# UM7_Schematic.net
KiCad netlist of a schematic drawn in Altium Designer
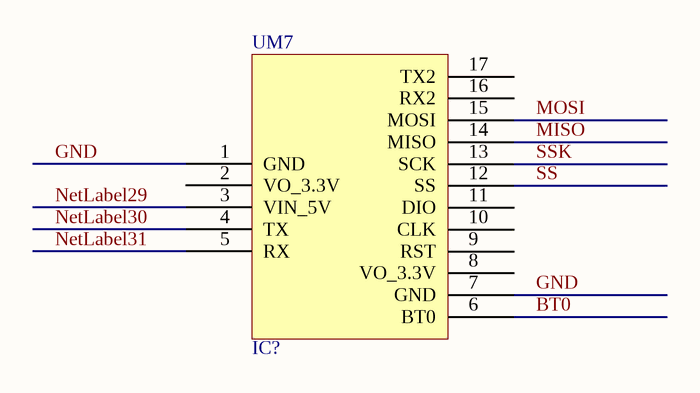
[diagram p0: UM7_Schematic.SchDoc]

(export (version "E")
  (design (tool "Eeschema 10.0.6"))
  (components (comp (ref "UM7") (value "IC?") (libsource (lib "UM7") (part "IC?"))))
  (nets
    (net (code "1") (name "/BT0") (class "Default")
      (node (ref "UM7") (pin "6") (pinfunction "BT0_6") (pintype "passive"))
    )
    (net (code "2") (name "/GND") (class "Default")
      (node (ref "UM7") (pin "1") (pinfunction "GND_1") (pintype "passive"))
      (node (ref "UM7") (pin "7") (pinfunction "GND_7") (pintype "passive"))
    )
    (net (code "3") (name "/MISO") (class "Default")
      (node (ref "UM7") (pin "14") (pinfunction "MISO_14") (pintype "passive"))
    )
    (net (code "4") (name "/MOSI") (class "Default")
      (node (ref "UM7") (pin "15") (pinfunction "MOSI_15") (pintype "passive"))
    )
    (net (code "5") (name "/NetLabel29") (class "Default")
      (node (ref "UM7") (pin "3") (pinfunction "VIN_5V_3") (pintype "passive"))
    )
    (net (code "6") (name "/NetLabel30") (class "Default")
      (node (ref "UM7") (pin "4") (pinfunction "TX_4") (pintype "passive"))
    )
    (net (code "7") (name "/NetLabel31") (class "Default")
      (node (ref "UM7") (pin "5") (pinfunction "RX_5") (pintype "passive"))
    )
    (net (code "8") (name "/SS") (class "Default")
      (node (ref "UM7") (pin "12") (pinfunction "SS_12") (pintype "passive"))
    )
    (net (code "9") (name "/SSK") (class "Default")
      (node (ref "UM7") (pin "13") (pinfunction "SCK_13") (pintype "passive"))
    )
    (net (code "10") (name "unconnected-(UM7-CLK-Pad10)") (class "Default")
      (node (ref "UM7") (pin "10") (pinfunction "CLK_10") (pintype "passive"))
    )
    (net (code "11") (name "unconnected-(UM7-DIO-Pad11)") (class "Default")
      (node (ref "UM7") (pin "11") (pinfunction "DIO_11") (pintype "passive"))
    )
    (net (code "12") (name "unconnected-(UM7-RST-Pad9)") (class "Default")
      (node (ref "UM7") (pin "9") (pinfunction "RST_9") (pintype "passive"))
    )
    (net (code "13") (name "unconnected-(UM7-RX2-Pad16)") (class "Default")
      (node (ref "UM7") (pin "16") (pinfunction "RX2_16") (pintype "passive"))
    )
    (net (code "14") (name "unconnected-(UM7-TX2-Pad17)") (class "Default")
      (node (ref "UM7") (pin "17") (pinfunction "TX2_17") (pintype "passive"))
    )
    (net (code "15") (name "unconnected-(UM7-VO_3.3V-Pad2)") (class "Default")
      (node (ref "UM7") (pin "2") (pinfunction "VO_3.3V_2") (pintype "passive"))
    )
    (net (code "16") (name "unconnected-(UM7-VO_3.3V-Pad8)") (class "Default")
      (node (ref "UM7") (pin "8") (pinfunction "VO_3.3V_8") (pintype "passive"))
    )
  )
)
